# Bosch2.net
KiCad netlist of a schematic drawn in Altium Designer
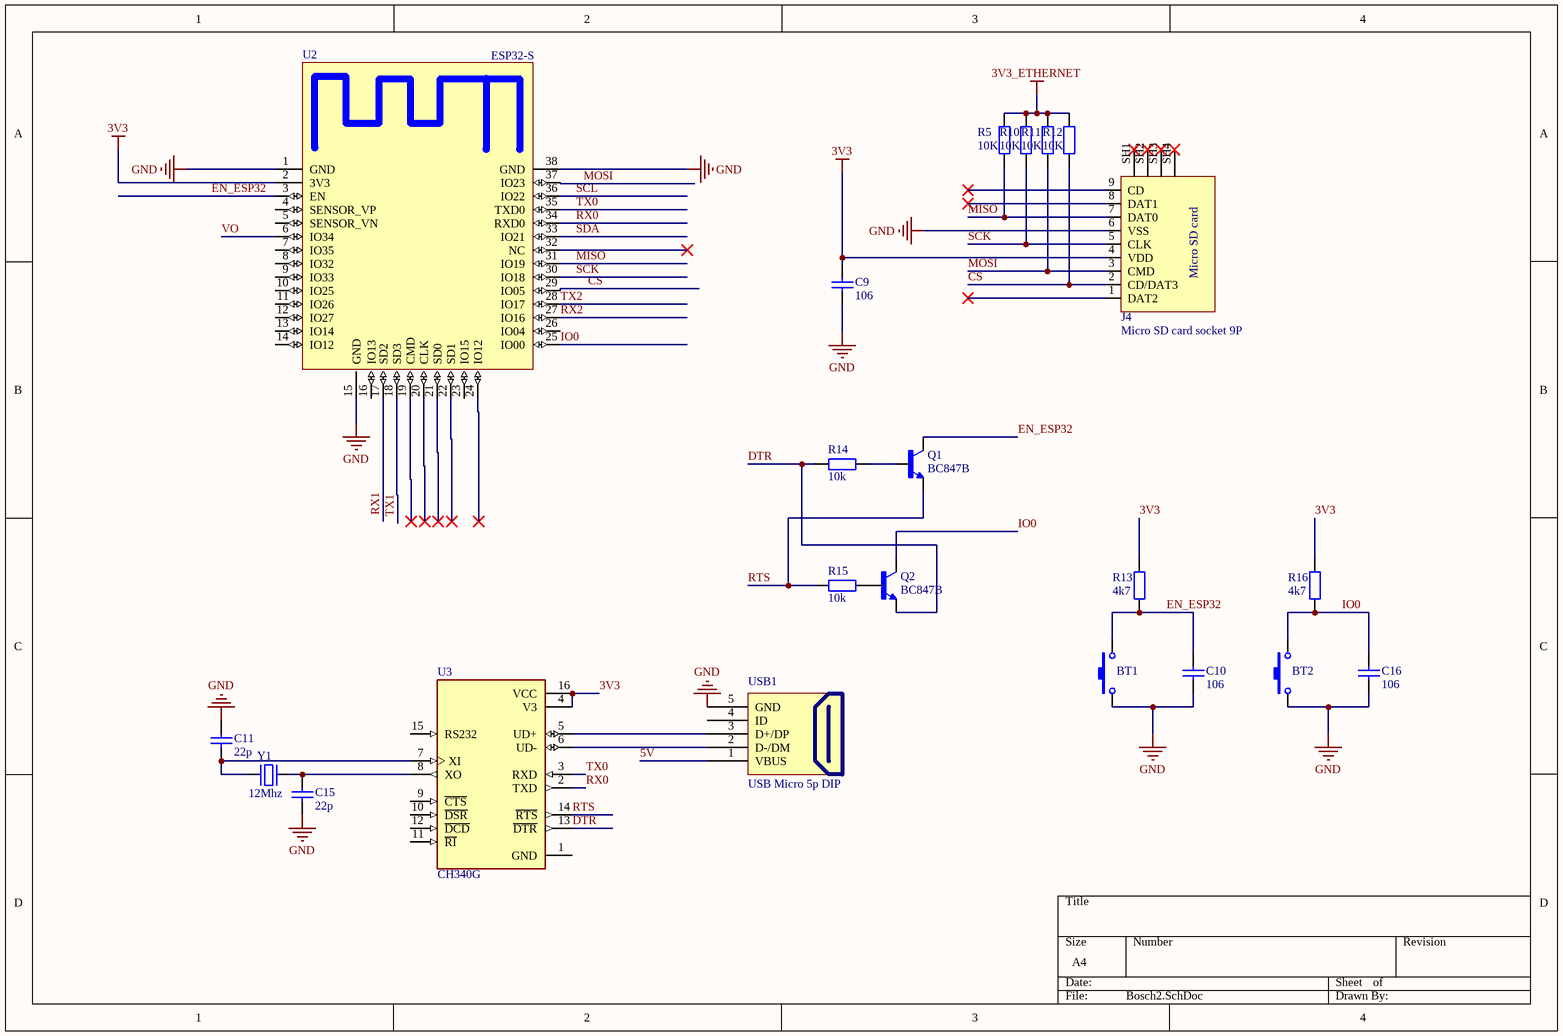
[diagram p0: Bosch2.SchDoc]

(export (version "E")
  (design (tool "Eeschema 10.0.6"))
  (components
    (comp (ref "BT1")
      (value "Nut Nhan 2 Chan SMD 3x6x2.5")
      (footprint "Nut Nhan 2 Chan SMD 3x6x2.5")
      (libsource (lib "Altium_Lib_by_KhueNguyenCreator") (part "Nut Nhan 2 Chan SMD 3x6x2.5"))
    )
    (comp (ref "BT2")
      (value "Nut Nhan 2 Chan SMD 3x6x2.5")
      (footprint "Nut Nhan 2 Chan SMD 3x6x2.5")
      (libsource (lib "Altium_Lib_by_KhueNguyenCreator") (part "Nut Nhan 2 Chan SMD 3x6x2.5"))
    )
    (comp (ref "C9")
      (value "106")
      (footprint "tu 0805")
      (description "Dán")
      (libsource (lib "Altium_Lib_by_KhueNguyenCreator") (part "Tu 0805 680pF 50V 10%"))
    )
    (comp (ref "C10")
      (value "106")
      (footprint "tu 0805")
      (description "Dán")
      (libsource (lib "Altium_Lib_by_KhueNguyenCreator") (part "Tu 0805 680pF 50V 10%"))
    )
    (comp (ref "C11")
      (value "22p")
      (footprint "tu 0805")
      (description "Dán")
      (libsource (lib "Altium_Lib_by_KhueNguyenCreator") (part "Tu 0805 680pF 50V 10%"))
    )
    (comp (ref "C15")
      (value "22p")
      (footprint "tu 0805")
      (description "Dán")
      (libsource (lib "Altium_Lib_by_KhueNguyenCreator") (part "Tu 0805 680pF 50V 10%"))
    )
    (comp (ref "C16")
      (value "106")
      (footprint "tu 0805")
      (description "Dán")
      (libsource (lib "Altium_Lib_by_KhueNguyenCreator") (part "Tu 0805 680pF 50V 10%"))
    )
    (comp (ref "J4")
      (value "Micro SD card socket 9P")
      (footprint "Micro SD card socket")
      (description "9 (8 + 1) Position Card Connector microSD Surface Mount, Right Angle Gold")
      (fields (field (name "MF") "Global Connector Technology") (field (name "MP") "MEM2075-00-140-01-A"))
      (libsource (lib "CMN") (part "Micro SD card socket 9P"))
    )
    (comp (ref "Q1")
      (value "BC847B")
      (footprint "TRANS_BC847B")
      (description "BJT, SOT-23, 45V, 100mA, NPN, 0.25W, 150C")
      (fields (field (name "MF") "Diotec Semiconductor"))
      (libsource (lib "BC847B") (part "BC847B"))
    )
    (comp (ref "Q2")
      (value "BC847B")
      (footprint "TRANS_BC847B")
      (description "BJT, SOT-23, 45V, 100mA, NPN, 0.25W, 150C")
      (fields (field (name "MF") "Diotec Semiconductor"))
      (libsource (lib "BC847B") (part "BC847B"))
    )
    (comp (ref "R5")
      (value "10K")
      (footprint "Tro SMD 0805")
      (description "Dán")
      (libsource (lib "Altium_Lib_by_KhueNguyenCreator") (part "Tro 0805 5% 820R"))
    )
    (comp (ref "R10")
      (value "10K")
      (footprint "Tro SMD 0805")
      (description "Dán")
      (libsource (lib "Altium_Lib_by_KhueNguyenCreator") (part "Tro 0805 5% 820R"))
    )
    (comp (ref "R11")
      (value "10K")
      (footprint "Tro SMD 0805")
      (description "Dán")
      (libsource (lib "Altium_Lib_by_KhueNguyenCreator") (part "Tro 0805 5% 820R"))
    )
    (comp (ref "R12")
      (value "10K")
      (footprint "Tro SMD 0805")
      (description "Dán")
      (libsource (lib "Altium_Lib_by_KhueNguyenCreator") (part "Tro 0805 5% 820R"))
    )
    (comp (ref "R13")
      (value "4k7")
      (footprint "Tro SMD 0805")
      (description "Dán")
      (libsource (lib "Altium_Lib_by_KhueNguyenCreator") (part "Tro 0805 5% 820R"))
    )
    (comp (ref "R14")
      (value "10k")
      (footprint "Tro SMD 0805")
      (description "Dán")
      (libsource (lib "Altium_Lib_by_KhueNguyenCreator") (part "Tro 0805 5% 820R"))
    )
    (comp (ref "R15")
      (value "10k")
      (footprint "Tro SMD 0805")
      (description "Dán")
      (libsource (lib "Altium_Lib_by_KhueNguyenCreator") (part "Tro 0805 5% 820R"))
    )
    (comp (ref "R16")
      (value "4k7")
      (footprint "Tro SMD 0805")
      (description "Dán")
      (libsource (lib "Altium_Lib_by_KhueNguyenCreator") (part "Tro 0805 5% 820R"))
    )
    (comp (ref "U2") (value "ESP32-S") (footprint "ESP32-S") (libsource (lib "CMN") (part "ESP32-S")))
    (comp (ref "U3")
      (value "CH340G")
      (footprint "SOIC127P600X180-16N")
      (description "USB Interface Integrated Circuit")
      (fields (field (name "MP") "Ch340G") (field (name "MF") "WCH"))
      (libsource (lib "CH340G") (part "CH340G"))
    )
    (comp (ref "USB1")
      (value "USB Micro 5p DIP")
      (footprint "USB Micro 5p DIP")
      (description "USB Type B")
      (libsource (lib "Altium_Lib_by_KhueNguyenCreator") (part "USB Micro 5p DIP"))
    )
    (comp (ref "Y1")
      (value "12Mhz")
      (footprint "Thach Anh 2 chan cam")
      (description "Crystal For all Crystal 2pin.")
      (libsource (lib "Altium_Lib_by_KhueNguyenCreator") (part "Thach Anh 2 chan Cam"))
    )
  )
  (nets
    (net (code "1") (name "/5V") (class "Default")
      (node (ref "USB1") (pin "1") (pinfunction "VBUS_1") (pintype "passive"))
    )
    (net (code "2") (name "/CS") (class "Default")
      (node (ref "J4") (pin "2") (pinfunction "CD/DAT3_2") (pintype "passive"))
      (node (ref "R12") (pin "1") (pinfunction "1_1") (pintype "passive"))
      (node (ref "U2") (pin "29") (pinfunction "IO05_29") (pintype "bidirectional"))
    )
    (net (code "3") (name "/DTR") (class "Default")
      (node (ref "Q2") (pin "2") (pinfunction "E_2") (pintype "passive"))
      (node (ref "R14") (pin "2") (pinfunction "2_2") (pintype "passive"))
      (node (ref "U3") (pin "13") (pinfunction "~{DTR}_13") (pintype "output"))
    )
    (net (code "4") (name "/EN_ESP32") (class "Default")
      (node (ref "BT1") (pin "2") (pinfunction "2_2") (pintype "passive"))
      (node (ref "C10") (pin "1") (pinfunction "1_1") (pintype "passive"))
      (node (ref "Q1") (pin "3") (pinfunction "C_3") (pintype "passive"))
      (node (ref "R13") (pin "1") (pinfunction "1_1") (pintype "passive"))
      (node (ref "U2") (pin "3") (pinfunction "EN_3") (pintype "bidirectional"))
    )
    (net (code "5") (name "/IO0") (class "Default")
      (node (ref "BT2") (pin "2") (pinfunction "2_2") (pintype "passive"))
      (node (ref "C16") (pin "1") (pinfunction "1_1") (pintype "passive"))
      (node (ref "Q2") (pin "3") (pinfunction "C_3") (pintype "passive"))
      (node (ref "R16") (pin "1") (pinfunction "1_1") (pintype "passive"))
      (node (ref "U2") (pin "25") (pinfunction "IO00_25") (pintype "bidirectional"))
    )
    (net (code "6") (name "/MISO") (class "Default")
      (node (ref "J4") (pin "7") (pinfunction "DAT0_7") (pintype "passive"))
      (node (ref "R5") (pin "1") (pinfunction "1_1") (pintype "passive"))
      (node (ref "U2") (pin "31") (pinfunction "IO19_31") (pintype "bidirectional"))
    )
    (net (code "7") (name "/MOSI") (class "Default")
      (node (ref "J4") (pin "3") (pinfunction "CMD_3") (pintype "passive"))
      (node (ref "R11") (pin "1") (pinfunction "1_1") (pintype "passive"))
      (node (ref "U2") (pin "37") (pinfunction "IO23_37") (pintype "bidirectional"))
    )
    (net (code "8") (name "/RTS") (class "Default")
      (node (ref "Q1") (pin "2") (pinfunction "E_2") (pintype "passive"))
      (node (ref "R15") (pin "2") (pinfunction "2_2") (pintype "passive"))
      (node (ref "U3") (pin "14") (pinfunction "~{RTS}_14") (pintype "output"))
    )
    (net (code "9") (name "/RX0") (class "Default")
      (node (ref "U2") (pin "34") (pinfunction "RXD0_34") (pintype "bidirectional"))
      (node (ref "U3") (pin "2") (pinfunction "TXD_2") (pintype "output"))
    )
    (net (code "10") (name "/RX1") (class "Default")
      (node (ref "U2") (pin "17") (pinfunction "SD2_17") (pintype "bidirectional"))
    )
    (net (code "11") (name "/RX2") (class "Default")
      (node (ref "U2") (pin "27") (pinfunction "IO16_27") (pintype "bidirectional"))
    )
    (net (code "12") (name "/SCK") (class "Default")
      (node (ref "J4") (pin "5") (pinfunction "CLK_5") (pintype "passive"))
      (node (ref "R10") (pin "1") (pinfunction "1_1") (pintype "passive"))
      (node (ref "U2") (pin "30") (pinfunction "IO18_30") (pintype "bidirectional"))
    )
    (net (code "13") (name "/SCL") (class "Default")
      (node (ref "U2") (pin "36") (pinfunction "IO22_36") (pintype "bidirectional"))
    )
    (net (code "14") (name "/SDA") (class "Default")
      (node (ref "U2") (pin "33") (pinfunction "IO21_33") (pintype "bidirectional"))
    )
    (net (code "15") (name "/TX0") (class "Default")
      (node (ref "U2") (pin "35") (pinfunction "TXD0_35") (pintype "bidirectional"))
      (node (ref "U3") (pin "3") (pinfunction "RXD_3") (pintype "input"))
    )
    (net (code "16") (name "/TX1") (class "Default")
      (node (ref "U2") (pin "18") (pinfunction "SD3_18") (pintype "bidirectional"))
    )
    (net (code "17") (name "/TX2") (class "Default")
      (node (ref "U2") (pin "28") (pinfunction "IO17_28") (pintype "bidirectional"))
    )
    (net (code "18") (name "/VO") (class "Default")
      (node (ref "U2") (pin "6") (pinfunction "IO34_6") (pintype "bidirectional"))
    )
    (net (code "19") (name "3V3") (class "Default")
      (node (ref "C9") (pin "1") (pinfunction "1_1") (pintype "passive"))
      (node (ref "J4") (pin "4") (pinfunction "VDD_4") (pintype "passive"))
      (node (ref "R13") (pin "2") (pinfunction "2_2") (pintype "passive"))
      (node (ref "R16") (pin "2") (pinfunction "2_2") (pintype "passive"))
      (node (ref "U2") (pin "2") (pinfunction "3V3_2") (pintype "power_in"))
      (node (ref "U3") (pin "16") (pinfunction "VCC_16") (pintype "power_in"))
      (node (ref "U3") (pin "4") (pinfunction "V3_4") (pintype "power_in"))
    )
    (net (code "20") (name "3V3_ETHERNET") (class "Default")
      (node (ref "R10") (pin "2") (pinfunction "2_2") (pintype "passive"))
      (node (ref "R11") (pin "2") (pinfunction "2_2") (pintype "passive"))
      (node (ref "R12") (pin "2") (pinfunction "2_2") (pintype "passive"))
      (node (ref "R5") (pin "2") (pinfunction "2_2") (pintype "passive"))
    )
    (net (code "21") (name "GND") (class "Default")
      (node (ref "BT1") (pin "1") (pinfunction "1_1") (pintype "passive"))
      (node (ref "BT2") (pin "1") (pinfunction "1_1") (pintype "passive"))
      (node (ref "C10") (pin "2") (pinfunction "2_2") (pintype "passive"))
      (node (ref "C11") (pin "1") (pinfunction "1_1") (pintype "passive"))
      (node (ref "C15") (pin "2") (pinfunction "2_2") (pintype "passive"))
      (node (ref "C16") (pin "2") (pinfunction "2_2") (pintype "passive"))
      (node (ref "C9") (pin "2") (pinfunction "2_2") (pintype "passive"))
      (node (ref "J4") (pin "6") (pinfunction "VSS_6") (pintype "passive"))
      (node (ref "U2") (pin "1") (pinfunction "GND_1") (pintype "power_in"))
      (node (ref "U2") (pin "15") (pinfunction "GND_15") (pintype "power_in"))
      (node (ref "U2") (pin "38") (pinfunction "GND_38") (pintype "power_in"))
      (node (ref "USB1") (pin "5") (pinfunction "GND_5") (pintype "passive"))
    )
    (net (code "22") (name "Net-(Q1-B)") (class "Default")
      (node (ref "Q1") (pin "1") (pinfunction "B_1") (pintype "passive"))
      (node (ref "R14") (pin "1") (pinfunction "1_1") (pintype "passive"))
    )
    (net (code "23") (name "Net-(Q2-B)") (class "Default")
      (node (ref "Q2") (pin "1") (pinfunction "B_1") (pintype "passive"))
      (node (ref "R15") (pin "1") (pinfunction "1_1") (pintype "passive"))
    )
    (net (code "24") (name "Net-(U3-UD+)") (class "Default")
      (node (ref "U3") (pin "5") (pinfunction "UD+_5") (pintype "bidirectional"))
      (node (ref "USB1") (pin "3") (pinfunction "D+/DP_3") (pintype "passive"))
    )
    (net (code "25") (name "Net-(U3-UD-)") (class "Default")
      (node (ref "U3") (pin "6") (pinfunction "UD-_6") (pintype "bidirectional"))
      (node (ref "USB1") (pin "2") (pinfunction "D-/DM_2") (pintype "passive"))
    )
    (net (code "26") (name "Net-(U3-XI)") (class "Default")
      (node (ref "C11") (pin "2") (pinfunction "2_2") (pintype "passive"))
      (node (ref "U3") (pin "7") (pinfunction "XI_7") (pintype "input"))
      (node (ref "Y1") (pin "1") (pinfunction "1_1") (pintype "passive"))
    )
    (net (code "27") (name "Net-(U3-XO)") (class "Default")
      (node (ref "C15") (pin "1") (pinfunction "1_1") (pintype "passive"))
      (node (ref "U3") (pin "8") (pinfunction "XO_8") (pintype "output"))
      (node (ref "Y1") (pin "2") (pinfunction "2_2") (pintype "passive"))
    )
    (net (code "28") (name "unconnected-(J4-CD-Pad9)") (class "Default")
      (node (ref "J4") (pin "9") (pinfunction "CD_9") (pintype "passive+no_connect"))
    )
    (net (code "29") (name "unconnected-(J4-DAT1-Pad8)") (class "Default")
      (node (ref "J4") (pin "8") (pinfunction "DAT1_8") (pintype "passive+no_connect"))
    )
    (net (code "30") (name "unconnected-(J4-DAT2-Pad1)") (class "Default")
      (node (ref "J4") (pin "1") (pinfunction "DAT2_1") (pintype "passive+no_connect"))
    )
    (net (code "31") (name "unconnected-(J4-SHIELD-PadSH1)") (class "Default")
      (node (ref "J4") (pin "SH1") (pinfunction "SHIELD_SH1") (pintype "power_in+no_connect"))
    )
    (net (code "32") (name "unconnected-(J4-SHIELD-PadSH2)") (class "Default")
      (node (ref "J4") (pin "SH2") (pinfunction "SHIELD_SH2") (pintype "power_in+no_connect"))
    )
    (net (code "33") (name "unconnected-(J4-SHIELD-PadSH3)") (class "Default")
      (node (ref "J4") (pin "SH3") (pinfunction "SHIELD_SH3") (pintype "power_in+no_connect"))
    )
    (net (code "34") (name "unconnected-(J4-SHIELD-PadSH4)") (class "Default")
      (node (ref "J4") (pin "SH4") (pinfunction "SHIELD_SH4") (pintype "power_in+no_connect"))
    )
    (net (code "35") (name "unconnected-(U2-CLK-Pad20)") (class "Default")
      (node (ref "U2") (pin "20") (pinfunction "CLK_20") (pintype "bidirectional+no_connect"))
    )
    (net (code "36") (name "unconnected-(U2-CMD-Pad19)") (class "Default")
      (node (ref "U2") (pin "19") (pinfunction "CMD_19") (pintype "bidirectional+no_connect"))
    )
    (net (code "37") (name "unconnected-(U2-IO04-Pad26)") (class "Default")
      (node (ref "U2") (pin "26") (pinfunction "IO04_26") (pintype "bidirectional"))
    )
    (net (code "38") (name "unconnected-(U2-IO12-Pad14)") (class "Default")
      (node (ref "U2") (pin "14") (pinfunction "IO12_14") (pintype "bidirectional"))
    )
    (net (code "39") (name "unconnected-(U2-IO12-Pad24)") (class "Default")
      (node (ref "U2") (pin "24") (pinfunction "IO12_24") (pintype "bidirectional+no_connect"))
    )
    (net (code "40") (name "unconnected-(U2-IO13-Pad16)") (class "Default")
      (node (ref "U2") (pin "16") (pinfunction "IO13_16") (pintype "bidirectional"))
    )
    (net (code "41") (name "unconnected-(U2-IO14-Pad13)") (class "Default")
      (node (ref "U2") (pin "13") (pinfunction "IO14_13") (pintype "bidirectional"))
    )
    (net (code "42") (name "unconnected-(U2-IO15-Pad23)") (class "Default")
      (node (ref "U2") (pin "23") (pinfunction "IO15_23") (pintype "bidirectional"))
    )
    (net (code "43") (name "unconnected-(U2-IO25-Pad10)") (class "Default")
      (node (ref "U2") (pin "10") (pinfunction "IO25_10") (pintype "bidirectional"))
    )
    (net (code "44") (name "unconnected-(U2-IO26-Pad11)") (class "Default")
      (node (ref "U2") (pin "11") (pinfunction "IO26_11") (pintype "bidirectional"))
    )
    (net (code "45") (name "unconnected-(U2-IO27-Pad12)") (class "Default")
      (node (ref "U2") (pin "12") (pinfunction "IO27_12") (pintype "bidirectional"))
    )
    (net (code "46") (name "unconnected-(U2-IO32-Pad8)") (class "Default")
      (node (ref "U2") (pin "8") (pinfunction "IO32_8") (pintype "bidirectional"))
    )
    (net (code "47") (name "unconnected-(U2-IO33-Pad9)") (class "Default")
      (node (ref "U2") (pin "9") (pinfunction "IO33_9") (pintype "bidirectional"))
    )
    (net (code "48") (name "unconnected-(U2-IO35-Pad7)") (class "Default")
      (node (ref "U2") (pin "7") (pinfunction "IO35_7") (pintype "bidirectional"))
    )
    (net (code "49") (name "unconnected-(U2-NC-Pad32)") (class "Default")
      (node (ref "U2") (pin "32") (pinfunction "NC_32") (pintype "bidirectional+no_connect"))
    )
    (net (code "50") (name "unconnected-(U2-SD0-Pad21)") (class "Default")
      (node (ref "U2") (pin "21") (pinfunction "SD0_21") (pintype "bidirectional+no_connect"))
    )
    (net (code "51") (name "unconnected-(U2-SD1-Pad22)") (class "Default")
      (node (ref "U2") (pin "22") (pinfunction "SD1_22") (pintype "bidirectional+no_connect"))
    )
    (net (code "52") (name "unconnected-(U2-SENSOR_VN-Pad5)") (class "Default")
      (node (ref "U2") (pin "5") (pinfunction "SENSOR_VN_5") (pintype "bidirectional"))
    )
    (net (code "53") (name "unconnected-(U2-SENSOR_VP-Pad4)") (class "Default")
      (node (ref "U2") (pin "4") (pinfunction "SENSOR_VP_4") (pintype "bidirectional"))
    )
    (net (code "54") (name "unconnected-(U3-GND-Pad1)") (class "Default")
      (node (ref "U3") (pin "1") (pinfunction "GND_1") (pintype "power_in"))
    )
    (net (code "55") (name "unconnected-(U3-RS232-Pad15)") (class "Default")
      (node (ref "U3") (pin "15") (pinfunction "RS232_15") (pintype "input"))
    )
    (net (code "56") (name "unconnected-(U3-~{CTS}-Pad9)") (class "Default")
      (node (ref "U3") (pin "9") (pinfunction "~{CTS}_9") (pintype "input"))
    )
    (net (code "57") (name "unconnected-(U3-~{DCD}-Pad12)") (class "Default")
      (node (ref "U3") (pin "12") (pinfunction "~{DCD}_12") (pintype "input"))
    )
    (net (code "58") (name "unconnected-(U3-~{DSR}-Pad10)") (class "Default")
      (node (ref "U3") (pin "10") (pinfunction "~{DSR}_10") (pintype "input"))
    )
    (net (code "59") (name "unconnected-(U3-~{RI}-Pad11)") (class "Default")
      (node (ref "U3") (pin "11") (pinfunction "~{RI}_11") (pintype "input"))
    )
    (net (code "60") (name "unconnected-(USB1-ID-Pad4)") (class "Default")
      (node (ref "USB1") (pin "4") (pinfunction "ID_4") (pintype "passive"))
    )
  )
)
